# transceiver.net
KiCad netlist of a schematic drawn in EAGLE
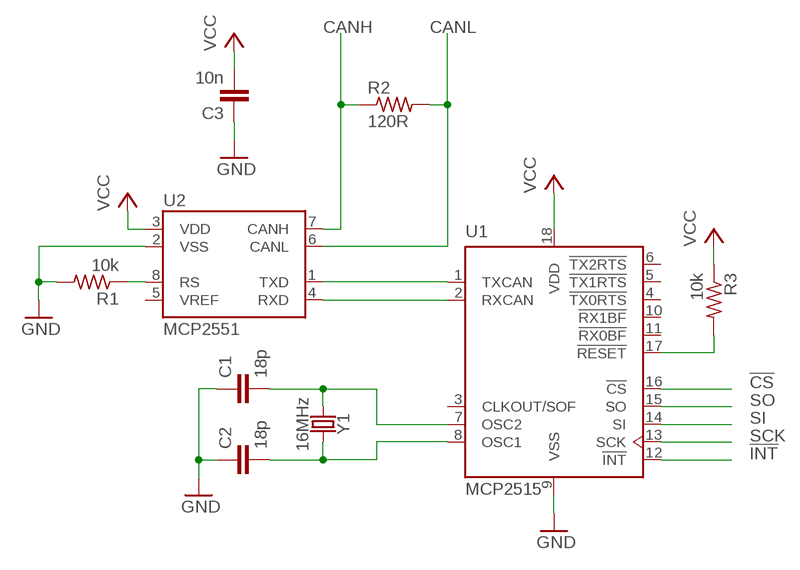
[diagram p0: schematic, sheet 1]

(export (version "E")
  (design (tool "Eeschema 10.0.6"))
  (components
    (comp (ref "C1")
      (value "18p")
      (footprint "eagle-import:C025-030X050")
      (libsource (lib "eagle-import") (part "C-EU025-030X050"))
    )
    (comp (ref "C2")
      (value "18p")
      (footprint "eagle-import:C025-030X050")
      (libsource (lib "eagle-import") (part "C-EU025-030X050"))
    )
    (comp (ref "C3")
      (value "10n")
      (footprint "eagle-import:C025-030X050")
      (libsource (lib "eagle-import") (part "C-EU025-030X050"))
    )
    (comp (ref "R1")
      (value "10k")
      (footprint "eagle-import:0204_7")
      (libsource (lib "eagle-import") (part "R-US_0204/7"))
    )
    (comp (ref "R2")
      (value "120R")
      (footprint "eagle-import:0204_7")
      (libsource (lib "eagle-import") (part "R-US_0204/7"))
    )
    (comp (ref "R3")
      (value "10k")
      (footprint "eagle-import:0204_7")
      (libsource (lib "eagle-import") (part "R-US_0204/7"))
    )
    (comp (ref "U1")
      (value "MCP2515")
      (footprint "eagle-import:DIL18")
      (libsource (lib "eagle-import") (part "MCP2515"))
    )
    (comp (ref "U2")
      (value "MCP2551")
      (footprint "eagle-import:DIL08")
      (libsource (lib "eagle-import") (part "MCP2551"))
    )
    (comp (ref "Y1")
      (value "16MHz")
      (footprint "eagle-import:HC49U")
      (libsource (lib "eagle-import") (part "CRYSTALPTH-HC49UV"))
    )
  )
  (nets
    (net (code "1") (name "/CANH") (class "Default")
      (node (ref "R2") (pin "1") (pinfunction "1_1") (pintype "passive"))
      (node (ref "U2") (pin "7") (pinfunction "CANH_7") (pintype "bidirectional"))
    )
    (net (code "2") (name "/CANL") (class "Default")
      (node (ref "R2") (pin "2") (pinfunction "2_2") (pintype "passive"))
      (node (ref "U2") (pin "6") (pinfunction "CANL_6") (pintype "bidirectional"))
    )
    (net (code "3") (name "/SCK") (class "Default")
      (node (ref "U1") (pin "13") (pinfunction "SCK_13") (pintype "input"))
    )
    (net (code "4") (name "/SI") (class "Default")
      (node (ref "U1") (pin "14") (pinfunction "SI_14") (pintype "input"))
    )
    (net (code "5") (name "/SO") (class "Default")
      (node (ref "U1") (pin "15") (pinfunction "SO_15") (pintype "output"))
    )
    (net (code "6") (name "/~{CS}") (class "Default")
      (node (ref "U1") (pin "16") (pinfunction "~{CS}_16") (pintype "input"))
    )
    (net (code "7") (name "/~{INT}") (class "Default")
      (node (ref "U1") (pin "12") (pinfunction "~{INT}_12") (pintype "output"))
    )
    (net (code "8") (name "GND") (class "Default")
      (node (ref "C1") (pin "1") (pinfunction "1_1") (pintype "passive"))
      (node (ref "C2") (pin "1") (pinfunction "1_1") (pintype "passive"))
      (node (ref "C3") (pin "1") (pinfunction "1_1") (pintype "passive"))
      (node (ref "R1") (pin "2") (pinfunction "2_2") (pintype "passive"))
      (node (ref "U1") (pin "9") (pinfunction "VSS_9") (pintype "power_in"))
      (node (ref "U2") (pin "2") (pinfunction "VSS_2") (pintype "power_in"))
    )
    (net (code "9") (name "Net-(U1-OSC1)") (class "Default")
      (node (ref "C2") (pin "2") (pinfunction "2_2") (pintype "passive"))
      (node (ref "U1") (pin "8") (pinfunction "OSC1_8") (pintype "bidirectional"))
      (node (ref "Y1") (pin "2") (pinfunction "2_2") (pintype "passive"))
    )
    (net (code "10") (name "Net-(U1-OSC2)") (class "Default")
      (node (ref "C1") (pin "2") (pinfunction "2_2") (pintype "passive"))
      (node (ref "U1") (pin "7") (pinfunction "OSC2_7") (pintype "bidirectional"))
      (node (ref "Y1") (pin "1") (pinfunction "1_1") (pintype "passive"))
    )
    (net (code "11") (name "Net-(U1-RXCAN)") (class "Default")
      (node (ref "U1") (pin "2") (pinfunction "RXCAN_2") (pintype "input"))
      (node (ref "U2") (pin "4") (pinfunction "RXD_4") (pintype "output"))
    )
    (net (code "12") (name "Net-(U1-TXCAN)") (class "Default")
      (node (ref "U1") (pin "1") (pinfunction "TXCAN_1") (pintype "output"))
      (node (ref "U2") (pin "1") (pinfunction "TXD_1") (pintype "input"))
    )
    (net (code "13") (name "Net-(U1-~{RESET})") (class "Default")
      (node (ref "R3") (pin "2") (pinfunction "2_2") (pintype "passive"))
      (node (ref "U1") (pin "17") (pinfunction "~{RESET}_17") (pintype "input"))
    )
    (net (code "14") (name "Net-(U2-RS)") (class "Default")
      (node (ref "R1") (pin "1") (pinfunction "1_1") (pintype "passive"))
      (node (ref "U2") (pin "8") (pinfunction "RS_8") (pintype "input"))
    )
    (net (code "15") (name "VCC") (class "Default")
      (node (ref "C3") (pin "2") (pinfunction "2_2") (pintype "passive"))
      (node (ref "R3") (pin "1") (pinfunction "1_1") (pintype "passive"))
      (node (ref "U1") (pin "18") (pinfunction "VDD_18") (pintype "power_in"))
      (node (ref "U2") (pin "3") (pinfunction "VDD_3") (pintype "power_in"))
    )
    (net (code "16") (name "unconnected-(U1-CLKOUT{slash}SOF-Pad3)") (class "Default")
      (node (ref "U1") (pin "3") (pinfunction "CLKOUT/SOF_3") (pintype "output"))
    )
    (net (code "17") (name "unconnected-(U1-~{RX0BF}-Pad11)") (class "Default")
      (node (ref "U1") (pin "11") (pinfunction "~{RX0BF}_11") (pintype "output"))
    )
    (net (code "18") (name "unconnected-(U1-~{RX1BF}-Pad10)") (class "Default")
      (node (ref "U1") (pin "10") (pinfunction "~{RX1BF}_10") (pintype "output"))
    )
    (net (code "19") (name "unconnected-(U1-~{TX0RTS}-Pad4)") (class "Default")
      (node (ref "U1") (pin "4") (pinfunction "~{TX0RTS}_4") (pintype "output"))
    )
    (net (code "20") (name "unconnected-(U1-~{TX1RTS}-Pad5)") (class "Default")
      (node (ref "U1") (pin "5") (pinfunction "~{TX1RTS}_5") (pintype "output"))
    )
    (net (code "21") (name "unconnected-(U1-~{TX2RTS}-Pad6)") (class "Default")
      (node (ref "U1") (pin "6") (pinfunction "~{TX2RTS}_6") (pintype "output"))
    )
    (net (code "22") (name "unconnected-(U2-VREF-Pad5)") (class "Default")
      (node (ref "U2") (pin "5") (pinfunction "VREF_5") (pintype "output"))
    )
  )
)
